# design4D.net
KiCad netlist of a schematic drawn in EAGLE
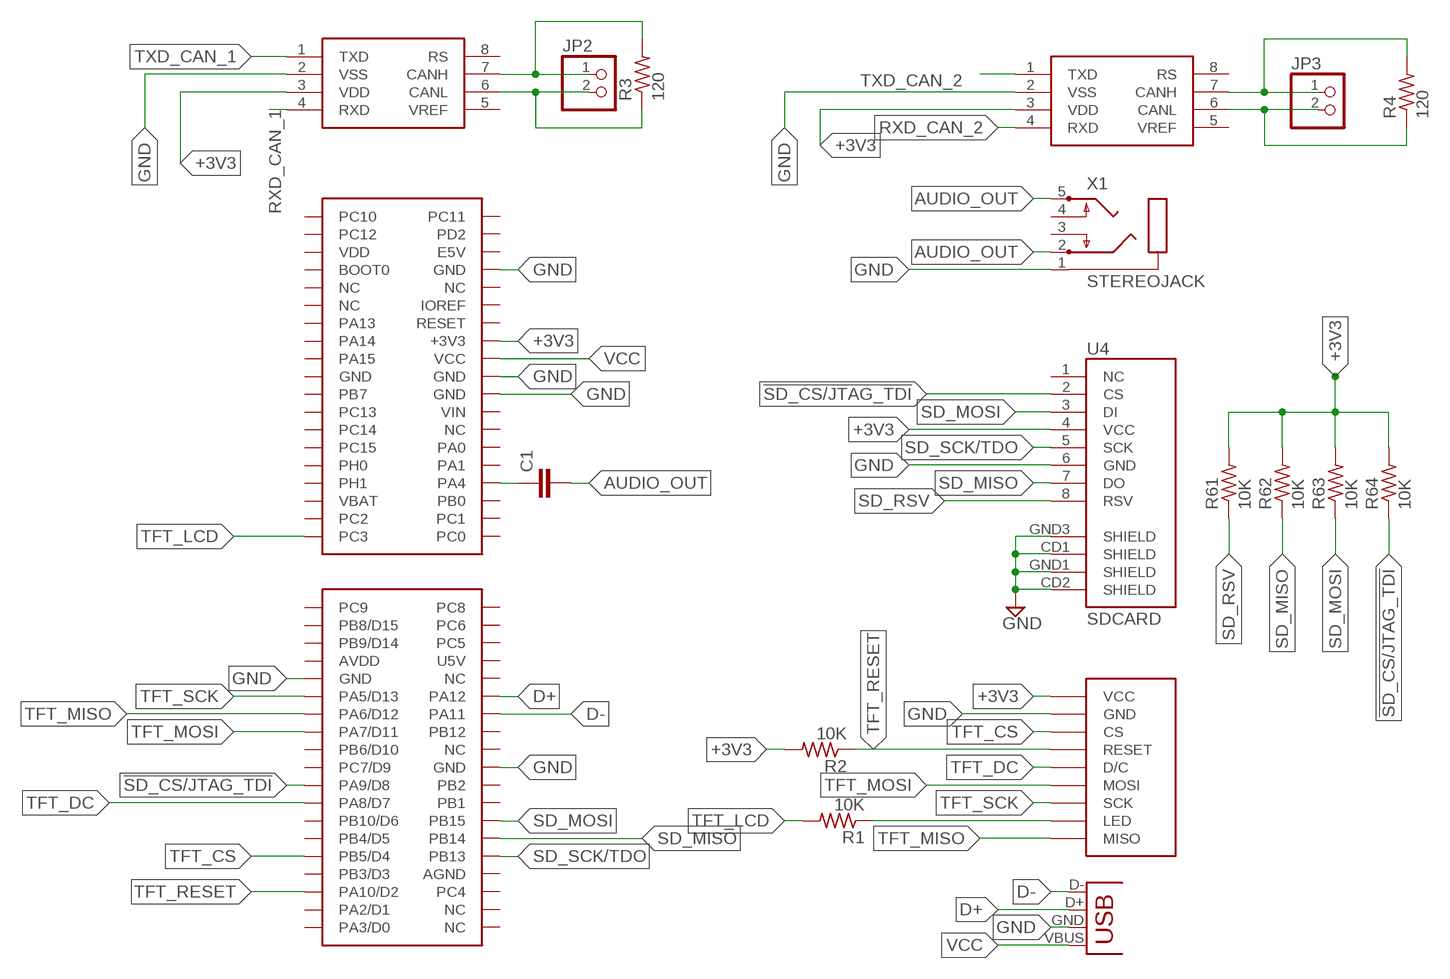
[diagram p0: schematic, sheet 1]

(export (version "E")
  (design (tool "Eeschema 10.0.6"))
  (components
    (comp (ref "C1")
      (value "CAP1206")
      (footprint "eagle-import:1206")
      (libsource (lib "eagle-import") (part "CAP1206"))
    )
    (comp (ref "J1")
      (value "SPI_TFT_DISPLAY")
      (footprint "eagle-import:SPI_DISPLAY")
      (libsource (lib "eagle-import") (part "SPI_TFT_DISPLAY"))
    )
    (comp (ref "JP1")
      (value "USB-A-H")
      (footprint "eagle-import:USB-A-H")
      (libsource (lib "eagle-import") (part "USB-A-H"))
    )
    (comp (ref "JP2")
      (value "HEADER-1X2")
      (footprint "eagle-import:1X02_OVAL")
      (libsource (lib "eagle-import") (part "HEADER-1X2"))
    )
    (comp (ref "JP3")
      (value "HEADER-1X2")
      (footprint "eagle-import:1X02_OVAL")
      (libsource (lib "eagle-import") (part "HEADER-1X2"))
    )
    (comp (ref "R1")
      (value "10K")
      (footprint "eagle-import:RLC_0603@1")
      (fields (field (name "MPN") "RMCF0603JT10K0"))
      (libsource (lib "eagle-import") (part "RESISTORRLC_0603"))
    )
    (comp (ref "R2")
      (value "10K")
      (footprint "eagle-import:RLC_0603@1")
      (fields (field (name "MPN") "RMCF0603JT10K0"))
      (libsource (lib "eagle-import") (part "RESISTORRLC_0603"))
    )
    (comp (ref "R3")
      (value "120")
      (footprint "eagle-import:RLC_0603@1")
      (fields (field (name "MPN") "RMCF0603JT10K0"))
      (libsource (lib "eagle-import") (part "RESISTORRLC_0603"))
    )
    (comp (ref "R4")
      (value "120")
      (footprint "eagle-import:RLC_0603@1")
      (fields (field (name "MPN") "RMCF0603JT10K0"))
      (libsource (lib "eagle-import") (part "RESISTORRLC_0603"))
    )
    (comp (ref "R61")
      (value "10K")
      (footprint "eagle-import:RLC_0603@1")
      (fields (field (name "MPN") "RMCF0603JT10K0"))
      (libsource (lib "eagle-import") (part "RESISTORRLC_0603"))
    )
    (comp (ref "R62")
      (value "10K")
      (footprint "eagle-import:RLC_0603@1")
      (fields (field (name "MPN") "RMCF0603JT10K0"))
      (libsource (lib "eagle-import") (part "RESISTORRLC_0603"))
    )
    (comp (ref "R63")
      (value "10K")
      (footprint "eagle-import:RLC_0603@1")
      (fields (field (name "MPN") "RMCF0603JT10K0"))
      (libsource (lib "eagle-import") (part "RESISTORRLC_0603"))
    )
    (comp (ref "R64")
      (value "10K")
      (footprint "eagle-import:RLC_0603@1")
      (fields (field (name "MPN") "RMCF0603JT10K0"))
      (libsource (lib "eagle-import") (part "RESISTORRLC_0603"))
    )
    (comp (ref "U$1")
      (value "MOPHOMOPHO_466RE")
      (footprint "eagle-import:MOPHO")
      (libsource (lib "eagle-import") (part "MOPHOMOPHO_466RE"))
    )
    (comp (ref "U1")
      (value "MCP2551")
      (footprint "eagle-import:SO08")
      (libsource (lib "eagle-import") (part "MCP2551"))
    )
    (comp (ref "U2")
      (value "MCP2551")
      (footprint "eagle-import:SO08")
      (libsource (lib "eagle-import") (part "MCP2551"))
    )
    (comp (ref "U4")
      (value "SDCARD")
      (footprint "eagle-import:MICRO-SD-SOCKET-PP")
      (libsource (lib "eagle-import") (part "USD-SOCKETNEW"))
    )
    (comp (ref "X1")
      (value "STEREOJACK")
      (footprint "eagle-import:STX3100")
      (libsource (lib "eagle-import") (part "STEREOJACK"))
    )
  )
  (nets
    (net (code "1") (name "+3V3") (class "Default")
      (node (ref "J1") (pin "VCC") (pinfunction "VCC_VCC") (pintype "power_in"))
      (node (ref "R2") (pin "2") (pinfunction "2_2") (pintype "passive"))
      (node (ref "R61") (pin "2") (pinfunction "2_2") (pintype "passive"))
      (node (ref "R62") (pin "2") (pinfunction "2_2") (pintype "passive"))
      (node (ref "R63") (pin "2") (pinfunction "2_2") (pintype "passive"))
      (node (ref "R64") (pin "2") (pinfunction "2_2") (pintype "passive"))
      (node (ref "U$1") (pin "P$16") (pinfunction "+3V3_P$16") (pintype "power_in"))
      (node (ref "U1") (pin "3") (pinfunction "VDD_3") (pintype "bidirectional"))
      (node (ref "U2") (pin "3") (pinfunction "VDD_3") (pintype "bidirectional"))
      (node (ref "U4") (pin "4") (pinfunction "VCC_4") (pintype "bidirectional"))
    )
    (net (code "2") (name "/AVDD") (class "Default")
      (node (ref "U$1") (pin "P$45") (pinfunction "AVDD_P$45") (pintype "power_in"))
    )
    (net (code "3") (name "/RXD_CAN_1") (class "Default")
      (node (ref "U2") (pin "4") (pinfunction "RXD_4") (pintype "bidirectional"))
    )
    (net (code "4") (name "/TXD_CAN_2") (class "Default")
      (node (ref "U1") (pin "1") (pinfunction "TXD_1") (pintype "bidirectional"))
    )
    (net (code "5") (name "/VBAT") (class "Default")
      (node (ref "U$1") (pin "P$33") (pinfunction "VBAT_P$33") (pintype "power_in"))
    )
    (net (code "6") (name "/VDD") (class "Default")
      (node (ref "U$1") (pin "P$5") (pinfunction "VDD_P$5") (pintype "power_in"))
    )
    (net (code "7") (name "/VIN") (class "Default")
      (node (ref "U$1") (pin "P$24") (pinfunction "VIN_P$24") (pintype "power_in"))
    )
    (net (code "8") (name "/~{SD_CS{slash}JTAG_TDI}") (class "Default")
      (node (ref "R64") (pin "1") (pinfunction "1_1") (pintype "passive"))
      (node (ref "U$1") (pin "P$59") (pinfunction "PA9/D8_P$59") (pintype "bidirectional"))
      (node (ref "U4") (pin "2") (pinfunction "CS_2") (pintype "bidirectional"))
    )
    (net (code "9") (name "AUDIO_OUT") (class "Default")
      (node (ref "C1") (pin "2") (pinfunction "2_2") (pintype "passive"))
      (node (ref "X1") (pin "2") (pinfunction "2_2") (pintype "passive"))
      (node (ref "X1") (pin "5") (pinfunction "5_5") (pintype "passive"))
    )
    (net (code "10") (name "D+") (class "Default")
      (node (ref "JP1") (pin "D+") (pinfunction "D-_D+") (pintype "bidirectional"))
      (node (ref "U$1") (pin "P$50") (pinfunction "PA12_P$50") (pintype "bidirectional"))
    )
    (net (code "11") (name "D-") (class "Default")
      (node (ref "JP1") (pin "D-") (pinfunction "D+_D-") (pintype "bidirectional"))
      (node (ref "U$1") (pin "P$52") (pinfunction "PA11_P$52") (pintype "bidirectional"))
    )
    (net (code "12") (name "GND") (class "Default")
      (node (ref "J1") (pin "GND") (pinfunction "GND_GND") (pintype "power_in"))
      (node (ref "JP1") (pin "GND") (pinfunction "VBUS_GND") (pintype "bidirectional"))
      (node (ref "U$1") (pin "P$20") (pinfunction "GND_P$20") (pintype "bidirectional"))
      (node (ref "U$1") (pin "P$22") (pinfunction "GND_P$22") (pintype "bidirectional"))
      (node (ref "U$1") (pin "P$47") (pinfunction "GND_P$47") (pintype "bidirectional"))
      (node (ref "U$1") (pin "P$58") (pinfunction "GND_P$58") (pintype "bidirectional"))
      (node (ref "U$1") (pin "P$8") (pinfunction "GND_P$8") (pintype "bidirectional"))
      (node (ref "U1") (pin "2") (pinfunction "VSS_2") (pintype "bidirectional"))
      (node (ref "U2") (pin "2") (pinfunction "VSS_2") (pintype "bidirectional"))
      (node (ref "U4") (pin "6") (pinfunction "GND_6") (pintype "bidirectional"))
      (node (ref "U4") (pin "CD1") (pinfunction "SHIELD_CD1") (pintype "bidirectional"))
      (node (ref "U4") (pin "CD2") (pinfunction "SHIELD_CD2") (pintype "bidirectional"))
      (node (ref "U4") (pin "GND1") (pinfunction "SHIELD_GND1") (pintype "bidirectional"))
      (node (ref "U4") (pin "GND3") (pinfunction "SHIELD_GND3") (pintype "bidirectional"))
      (node (ref "X1") (pin "1") (pinfunction "1_1") (pintype "passive"))
    )
    (net (code "13") (name "Net-(J1-PadLED)") (class "Default")
      (node (ref "J1") (pin "LED") (pinfunction "LED_LED") (pintype "bidirectional"))
      (node (ref "R1") (pin "1") (pinfunction "1_1") (pintype "passive"))
    )
    (net (code "14") (name "Net-(U$1-PA4)") (class "Default")
      (node (ref "C1") (pin "1") (pinfunction "1_1") (pintype "passive"))
      (node (ref "U$1") (pin "P$32") (pinfunction "PA4_P$32") (pintype "bidirectional"))
    )
    (net (code "15") (name "Net-(U1-CANH)") (class "Default")
      (node (ref "JP3") (pin "1") (pinfunction "1_1") (pintype "passive"))
      (node (ref "R4") (pin "2") (pinfunction "2_2") (pintype "passive"))
      (node (ref "U1") (pin "7") (pinfunction "CANH_7") (pintype "bidirectional"))
    )
    (net (code "16") (name "Net-(U1-CANL)") (class "Default")
      (node (ref "JP3") (pin "2") (pinfunction "2_2") (pintype "passive"))
      (node (ref "R4") (pin "1") (pinfunction "1_1") (pintype "passive"))
      (node (ref "U1") (pin "6") (pinfunction "CANL_6") (pintype "bidirectional"))
    )
    (net (code "17") (name "Net-(U2-CANH)") (class "Default")
      (node (ref "JP2") (pin "1") (pinfunction "1_1") (pintype "passive"))
      (node (ref "R3") (pin "2") (pinfunction "2_2") (pintype "passive"))
      (node (ref "U2") (pin "7") (pinfunction "CANH_7") (pintype "bidirectional"))
    )
    (net (code "18") (name "Net-(U2-CANL)") (class "Default")
      (node (ref "JP2") (pin "2") (pinfunction "2_2") (pintype "passive"))
      (node (ref "R3") (pin "1") (pinfunction "1_1") (pintype "passive"))
      (node (ref "U2") (pin "6") (pinfunction "CANL_6") (pintype "bidirectional"))
    )
    (net (code "19") (name "RXD_CAN_2") (class "Default")
      (node (ref "U1") (pin "4") (pinfunction "RXD_4") (pintype "bidirectional"))
    )
    (net (code "20") (name "SD_MISO") (class "Default")
      (node (ref "R62") (pin "1") (pinfunction "1_1") (pintype "passive"))
      (node (ref "U$1") (pin "P$66") (pinfunction "PB14_P$66") (pintype "bidirectional"))
      (node (ref "U4") (pin "7") (pinfunction "DO_7") (pintype "bidirectional"))
    )
    (net (code "21") (name "SD_MOSI") (class "Default")
      (node (ref "R63") (pin "1") (pinfunction "1_1") (pintype "passive"))
      (node (ref "U$1") (pin "P$64") (pinfunction "PB15_P$64") (pintype "bidirectional"))
      (node (ref "U4") (pin "3") (pinfunction "DI_3") (pintype "bidirectional"))
    )
    (net (code "22") (name "SD_RSV") (class "Default")
      (node (ref "R61") (pin "1") (pinfunction "1_1") (pintype "passive"))
      (node (ref "U4") (pin "8") (pinfunction "RSV_8") (pintype "bidirectional"))
    )
    (net (code "23") (name "SD_SCK{slash}TDO") (class "Default")
      (node (ref "U$1") (pin "P$68") (pinfunction "PB13_P$68") (pintype "bidirectional"))
      (node (ref "U4") (pin "5") (pinfunction "SCK_5") (pintype "bidirectional"))
    )
    (net (code "24") (name "TFT_CS") (class "Default")
      (node (ref "J1") (pin "CS") (pinfunction "CS_CS") (pintype "bidirectional"))
      (node (ref "U$1") (pin "P$67") (pinfunction "PB5/D4_P$67") (pintype "bidirectional"))
    )
    (net (code "25") (name "TFT_DC") (class "Default")
      (node (ref "J1") (pin "D/C") (pinfunction "D/C_D/C") (pintype "bidirectional"))
      (node (ref "U$1") (pin "P$61") (pinfunction "PA8/D7_P$61") (pintype "bidirectional"))
    )
    (net (code "26") (name "TFT_LCD") (class "Default")
      (node (ref "R1") (pin "2") (pinfunction "2_2") (pintype "passive"))
      (node (ref "U$1") (pin "P$37") (pinfunction "PC3_P$37") (pintype "bidirectional"))
    )
    (net (code "27") (name "TFT_MISO") (class "Default")
      (node (ref "J1") (pin "MISO") (pinfunction "MISO_MISO") (pintype "bidirectional"))
      (node (ref "U$1") (pin "P$51") (pinfunction "PA6/D12_P$51") (pintype "bidirectional"))
    )
    (net (code "28") (name "TFT_MOSI") (class "Default")
      (node (ref "J1") (pin "MOSI") (pinfunction "MOSI_MOSI") (pintype "bidirectional"))
      (node (ref "U$1") (pin "P$53") (pinfunction "PA7/D11_P$53") (pintype "bidirectional"))
    )
    (net (code "29") (name "TFT_RESET") (class "Default")
      (node (ref "J1") (pin "RESET") (pinfunction "RESET_RESET") (pintype "bidirectional"))
      (node (ref "R2") (pin "1") (pinfunction "1_1") (pintype "passive"))
      (node (ref "U$1") (pin "P$71") (pinfunction "PA10/D2_P$71") (pintype "bidirectional"))
    )
    (net (code "30") (name "TFT_SCK") (class "Default")
      (node (ref "J1") (pin "SCK") (pinfunction "SCK_SCK") (pintype "bidirectional"))
      (node (ref "U$1") (pin "P$49") (pinfunction "PA5/D13_P$49") (pintype "bidirectional"))
    )
    (net (code "31") (name "TXD_CAN_1") (class "Default")
      (node (ref "U2") (pin "1") (pinfunction "TXD_1") (pintype "bidirectional"))
    )
    (net (code "32") (name "VCC") (class "Default")
      (node (ref "JP1") (pin "VBUS") (pinfunction "GND_VBUS") (pintype "bidirectional"))
      (node (ref "U$1") (pin "P$18") (pinfunction "VCC_P$18") (pintype "power_in"))
    )
    (net (code "33") (name "unconnected-(U$1-AGND-PadP$70)") (class "Default")
      (node (ref "U$1") (pin "P$70") (pinfunction "AGND_P$70") (pintype "bidirectional"))
    )
    (net (code "34") (name "unconnected-(U$1-BOOT0-PadP$7)") (class "Default")
      (node (ref "U$1") (pin "P$7") (pinfunction "BOOT0_P$7") (pintype "bidirectional"))
    )
    (net (code "35") (name "unconnected-(U$1-E5V-PadP$6)") (class "Default")
      (node (ref "U$1") (pin "P$6") (pinfunction "E5V_P$6") (pintype "bidirectional"))
    )
    (net (code "36") (name "unconnected-(U$1-GND-PadP$19)") (class "Default")
      (node (ref "U$1") (pin "P$19") (pinfunction "GND_P$19") (pintype "bidirectional"))
    )
    (net (code "37") (name "unconnected-(U$1-IOREF-PadP$12)") (class "Default")
      (node (ref "U$1") (pin "P$12") (pinfunction "IOREF_P$12") (pintype "bidirectional"))
    )
    (net (code "38") (name "unconnected-(U$1-NC-PadP$9)") (class "Default")
      (node (ref "U$1") (pin "P$9") (pinfunction "NC_P$9") (pintype "bidirectional"))
    )
    (net (code "39") (name "unconnected-(U$1-NC-PadP$10)") (class "Default")
      (node (ref "U$1") (pin "P$10") (pinfunction "NC_P$10") (pintype "bidirectional"))
    )
    (net (code "40") (name "unconnected-(U$1-NC-PadP$11)") (class "Default")
      (node (ref "U$1") (pin "P$11") (pinfunction "NC_P$11") (pintype "bidirectional"))
    )
    (net (code "41") (name "unconnected-(U$1-NC-PadP$26)") (class "Default")
      (node (ref "U$1") (pin "P$26") (pinfunction "NC_P$26") (pintype "bidirectional"))
    )
    (net (code "42") (name "unconnected-(U$1-NC-PadP$48)") (class "Default")
      (node (ref "U$1") (pin "P$48") (pinfunction "NC_P$48") (pintype "bidirectional"))
    )
    (net (code "43") (name "unconnected-(U$1-NC-PadP$56)") (class "Default")
      (node (ref "U$1") (pin "P$56") (pinfunction "NC_P$56") (pintype "bidirectional"))
    )
    (net (code "44") (name "unconnected-(U$1-NC-PadP$74)") (class "Default")
      (node (ref "U$1") (pin "P$74") (pinfunction "NC_P$74") (pintype "bidirectional"))
    )
    (net (code "45") (name "unconnected-(U$1-NC-PadP$76)") (class "Default")
      (node (ref "U$1") (pin "P$76") (pinfunction "NC_P$76") (pintype "bidirectional"))
    )
    (net (code "46") (name "unconnected-(U$1-PA0-PadP$28)") (class "Default")
      (node (ref "U$1") (pin "P$28") (pinfunction "PA0_P$28") (pintype "bidirectional"))
    )
    (net (code "47") (name "unconnected-(U$1-PA1-PadP$30)") (class "Default")
      (node (ref "U$1") (pin "P$30") (pinfunction "PA1_P$30") (pintype "bidirectional"))
    )
    (net (code "48") (name "unconnected-(U$1-PA2{slash}D1-PadP$73)") (class "Default")
      (node (ref "U$1") (pin "P$73") (pinfunction "PA2/D1_P$73") (pintype "bidirectional"))
    )
    (net (code "49") (name "unconnected-(U$1-PA3{slash}D0-PadP$75)") (class "Default")
      (node (ref "U$1") (pin "P$75") (pinfunction "PA3/D0_P$75") (pintype "bidirectional"))
    )
    (net (code "50") (name "unconnected-(U$1-PA13-PadP$13)") (class "Default")
      (node (ref "U$1") (pin "P$13") (pinfunction "PA13_P$13") (pintype "bidirectional"))
    )
    (net (code "51") (name "unconnected-(U$1-PA14-PadP$15)") (class "Default")
      (node (ref "U$1") (pin "P$15") (pinfunction "PA14_P$15") (pintype "bidirectional"))
    )
    (net (code "52") (name "unconnected-(U$1-PA15-PadP$17)") (class "Default")
      (node (ref "U$1") (pin "P$17") (pinfunction "PA15_P$17") (pintype "bidirectional"))
    )
    (net (code "53") (name "unconnected-(U$1-PB0-PadP$34)") (class "Default")
      (node (ref "U$1") (pin "P$34") (pinfunction "PB0_P$34") (pintype "bidirectional"))
    )
    (net (code "54") (name "unconnected-(U$1-PB1-PadP$62)") (class "Default")
      (node (ref "U$1") (pin "P$62") (pinfunction "PB1_P$62") (pintype "bidirectional"))
    )
    (net (code "55") (name "unconnected-(U$1-PB2-PadP$60)") (class "Default")
      (node (ref "U$1") (pin "P$60") (pinfunction "PB2_P$60") (pintype "bidirectional"))
    )
    (net (code "56") (name "unconnected-(U$1-PB3{slash}D3-PadP$69)") (class "Default")
      (node (ref "U$1") (pin "P$69") (pinfunction "PB3/D3_P$69") (pintype "bidirectional"))
    )
    (net (code "57") (name "unconnected-(U$1-PB4{slash}D5-PadP$65)") (class "Default")
      (node (ref "U$1") (pin "P$65") (pinfunction "PB4/D5_P$65") (pintype "bidirectional"))
    )
    (net (code "58") (name "unconnected-(U$1-PB6{slash}D10-PadP$55)") (class "Default")
      (node (ref "U$1") (pin "P$55") (pinfunction "PB6/D10_P$55") (pintype "bidirectional"))
    )
    (net (code "59") (name "unconnected-(U$1-PB7-PadP$21)") (class "Default")
      (node (ref "U$1") (pin "P$21") (pinfunction "PB7_P$21") (pintype "bidirectional"))
    )
    (net (code "60") (name "unconnected-(U$1-PB8{slash}D15-PadP$41)") (class "Default")
      (node (ref "U$1") (pin "P$41") (pinfunction "PB8/D15_P$41") (pintype "bidirectional"))
    )
    (net (code "61") (name "unconnected-(U$1-PB9{slash}D14-PadP$43)") (class "Default")
      (node (ref "U$1") (pin "P$43") (pinfunction "PB9/D14_P$43") (pintype "bidirectional"))
    )
    (net (code "62") (name "unconnected-(U$1-PB10{slash}D6-PadP$63)") (class "Default")
      (node (ref "U$1") (pin "P$63") (pinfunction "PB10/D6_P$63") (pintype "bidirectional"))
    )
    (net (code "63") (name "unconnected-(U$1-PB12-PadP$54)") (class "Default")
      (node (ref "U$1") (pin "P$54") (pinfunction "PB12_P$54") (pintype "bidirectional"))
    )
    (net (code "64") (name "unconnected-(U$1-PC0-PadP$38)") (class "Default")
      (node (ref "U$1") (pin "P$38") (pinfunction "PC0_P$38") (pintype "bidirectional"))
    )
    (net (code "65") (name "unconnected-(U$1-PC1-PadP$36)") (class "Default")
      (node (ref "U$1") (pin "P$36") (pinfunction "PC1_P$36") (pintype "bidirectional"))
    )
    (net (code "66") (name "unconnected-(U$1-PC2-PadP$35)") (class "Default")
      (node (ref "U$1") (pin "P$35") (pinfunction "PC2_P$35") (pintype "bidirectional"))
    )
    (net (code "67") (name "unconnected-(U$1-PC4-PadP$72)") (class "Default")
      (node (ref "U$1") (pin "P$72") (pinfunction "PC4_P$72") (pintype "bidirectional"))
    )
    (net (code "68") (name "unconnected-(U$1-PC5-PadP$44)") (class "Default")
      (node (ref "U$1") (pin "P$44") (pinfunction "PC5_P$44") (pintype "bidirectional"))
    )
    (net (code "69") (name "unconnected-(U$1-PC6-PadP$42)") (class "Default")
      (node (ref "U$1") (pin "P$42") (pinfunction "PC6_P$42") (pintype "bidirectional"))
    )
    (net (code "70") (name "unconnected-(U$1-PC7{slash}D9-PadP$57)") (class "Default")
      (node (ref "U$1") (pin "P$57") (pinfunction "PC7/D9_P$57") (pintype "bidirectional"))
    )
    (net (code "71") (name "unconnected-(U$1-PC8-PadP$40)") (class "Default")
      (node (ref "U$1") (pin "P$40") (pinfunction "PC8_P$40") (pintype "bidirectional"))
    )
    (net (code "72") (name "unconnected-(U$1-PC9-PadP$39)") (class "Default")
      (node (ref "U$1") (pin "P$39") (pinfunction "PC9_P$39") (pintype "bidirectional"))
    )
    (net (code "73") (name "unconnected-(U$1-PC10-PadP$1)") (class "Default")
      (node (ref "U$1") (pin "P$1") (pinfunction "PC10_P$1") (pintype "bidirectional"))
    )
    (net (code "74") (name "unconnected-(U$1-PC11-PadP$2)") (class "Default")
      (node (ref "U$1") (pin "P$2") (pinfunction "PC11_P$2") (pintype "bidirectional"))
    )
    (net (code "75") (name "unconnected-(U$1-PC12-PadP$3)") (class "Default")
      (node (ref "U$1") (pin "P$3") (pinfunction "PC12_P$3") (pintype "bidirectional"))
    )
    (net (code "76") (name "unconnected-(U$1-PC13-PadP$23)") (class "Default")
      (node (ref "U$1") (pin "P$23") (pinfunction "PC13_P$23") (pintype "bidirectional"))
    )
    (net (code "77") (name "unconnected-(U$1-PC14-PadP$25)") (class "Default")
      (node (ref "U$1") (pin "P$25") (pinfunction "PC14_P$25") (pintype "bidirectional"))
    )
    (net (code "78") (name "unconnected-(U$1-PC15-PadP$27)") (class "Default")
      (node (ref "U$1") (pin "P$27") (pinfunction "PC15_P$27") (pintype "bidirectional"))
    )
    (net (code "79") (name "unconnected-(U$1-PD2-PadP$4)") (class "Default")
      (node (ref "U$1") (pin "P$4") (pinfunction "PD2_P$4") (pintype "bidirectional"))
    )
    (net (code "80") (name "unconnected-(U$1-PH0-PadP$29)") (class "Default")
      (node (ref "U$1") (pin "P$29") (pinfunction "PH0_P$29") (pintype "bidirectional"))
    )
    (net (code "81") (name "unconnected-(U$1-PH1-PadP$31)") (class "Default")
      (node (ref "U$1") (pin "P$31") (pinfunction "PH1_P$31") (pintype "bidirectional"))
    )
    (net (code "82") (name "unconnected-(U$1-RESET-PadP$14)") (class "Default")
      (node (ref "U$1") (pin "P$14") (pinfunction "RESET_P$14") (pintype "bidirectional"))
    )
    (net (code "83") (name "unconnected-(U$1-U5V-PadP$46)") (class "Default")
      (node (ref "U$1") (pin "P$46") (pinfunction "U5V_P$46") (pintype "bidirectional"))
    )
    (net (code "84") (name "unconnected-(U1-RS-Pad8)") (class "Default")
      (node (ref "U1") (pin "8") (pinfunction "RS_8") (pintype "bidirectional"))
    )
    (net (code "85") (name "unconnected-(U1-VREF-Pad5)") (class "Default")
      (node (ref "U1") (pin "5") (pinfunction "VREF_5") (pintype "bidirectional"))
    )
    (net (code "86") (name "unconnected-(U2-RS-Pad8)") (class "Default")
      (node (ref "U2") (pin "8") (pinfunction "RS_8") (pintype "bidirectional"))
    )
    (net (code "87") (name "unconnected-(U2-VREF-Pad5)") (class "Default")
      (node (ref "U2") (pin "5") (pinfunction "VREF_5") (pintype "bidirectional"))
    )
    (net (code "88") (name "unconnected-(U4-NC-Pad1)") (class "Default")
      (node (ref "U4") (pin "1") (pinfunction "NC_1") (pintype "bidirectional"))
    )
    (net (code "89") (name "unconnected-(X1-Pad3)") (class "Default")
      (node (ref "X1") (pin "3") (pinfunction "3_3") (pintype "passive"))
    )
    (net (code "90") (name "unconnected-(X1-Pad4)") (class "Default")
      (node (ref "X1") (pin "4") (pinfunction "4_4") (pintype "passive"))
    )
  )
)
